# Sheet2.net
KiCad netlist of a schematic drawn in Altium Designer
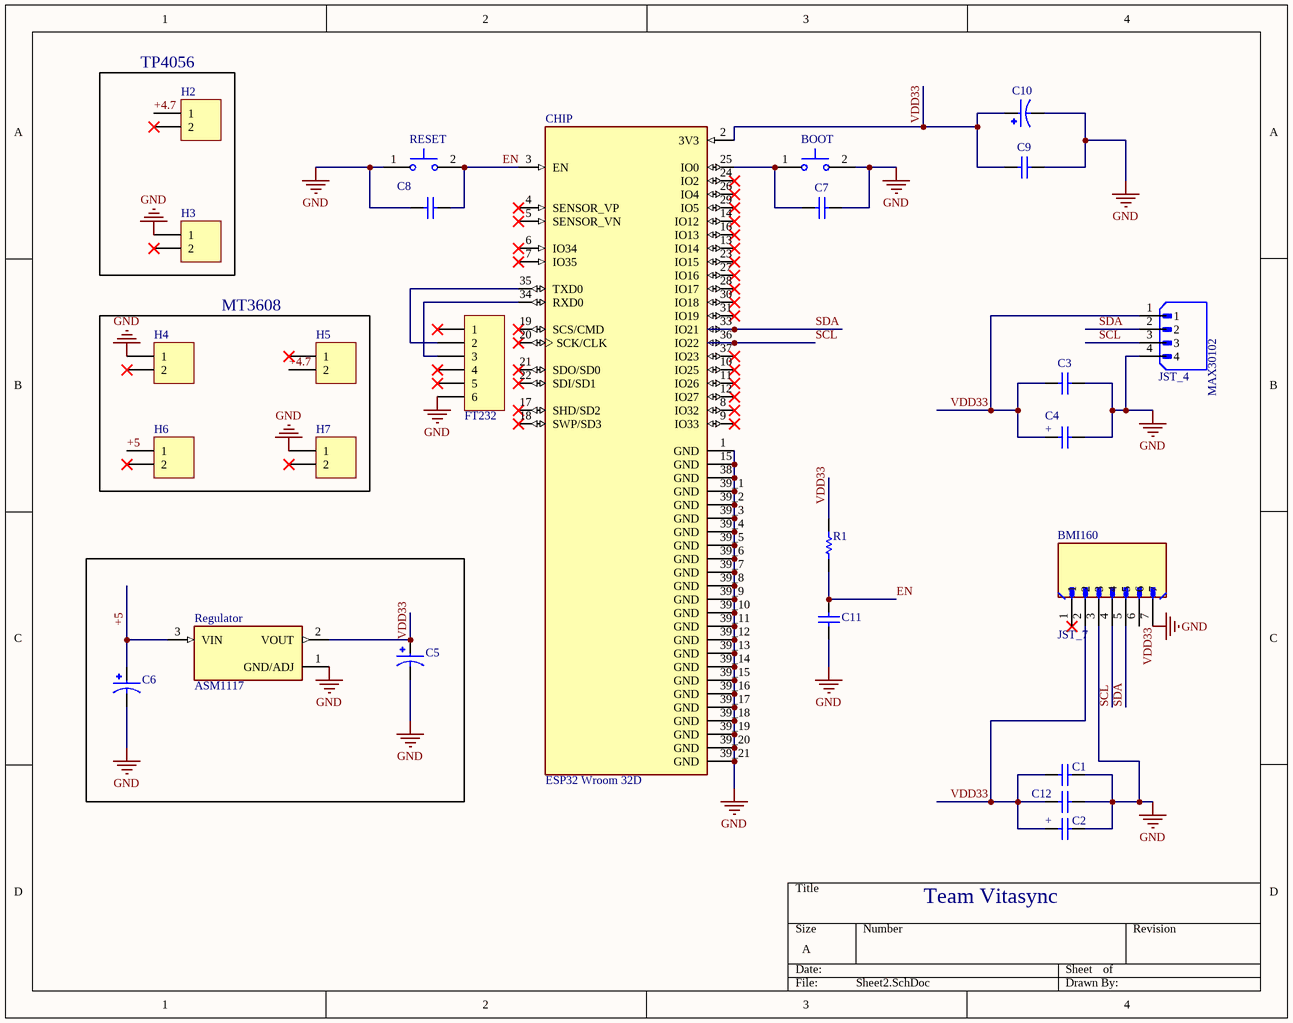
[diagram p0: Sheet2.SchDoc]

(export (version "E")
  (design (tool "Eeschema 10.0.6"))
  (components
    (comp (ref "BMI160") (value "JST_7") (footprint "JST_7") (libsource (lib "SPO2") (part "JST_7")))
    (comp (ref "BOOT")
      (value "~")
      (footprint "SW_BUTT-2")
      (description "Tactile Switches MINI PUSH BUTTON SWITCH 2-PIN QTY. 4")
      (fields (field (name "MF") "Gravitech") (field (name "MP") "BUTT-2"))
      (libsource (lib "SPO2") (part "BUTT-2"))
    )
    (comp (ref "C1")
      (value "Ceramic Capacitor")
      (footprint "Ceramic Capacitor")
      (libsource (lib "SPO2") (part "Ceramic Capacitor"))
    )
    (comp (ref "C2")
      (value "Capacitor 10uF")
      (footprint "Capacitor 10uF")
      (libsource (lib "SPO2") (part "Capacitor 10uF"))
    )
    (comp (ref "C3")
      (value "Ceramic Capacitor")
      (footprint "Ceramic Capacitor")
      (libsource (lib "SPO2") (part "Ceramic Capacitor"))
    )
    (comp (ref "C4")
      (value "Capacitor 10uF")
      (footprint "Capacitor 10uF")
      (libsource (lib "SPO2") (part "Capacitor 10uF"))
    )
    (comp (ref "C5")
      (value "EEUHD1H220")
      (footprint "CAPPRD250W50D500H1100")
      (description "Cap Aluminum Lytic 22uF 50V 20% (5 X 11mm) Radial 2.5mm 65mA 1000h 105C Bulk")
      (fields (field (name "MF") "Panasonic") (field (name "MP") "EEU-HD1H220"))
      (libsource (lib "SPO2") (part "EEUHD1H220"))
    )
    (comp (ref "C6")
      (value "EEUHD1H220")
      (footprint "CAPPRD250W50D500H1100")
      (description "Cap Aluminum Lytic 22uF 50V 20% (5 X 11mm) Radial 2.5mm 65mA 1000h 105C Bulk")
      (fields (field (name "MF") "Panasonic") (field (name "MP") "EEU-HD1H220"))
      (libsource (lib "SPO2") (part "EEUHD1H220"))
    )
    (comp (ref "C7")
      (value "Ceramic Capacitor")
      (footprint "Ceramic Capacitor")
      (libsource (lib "SPO2") (part "Ceramic Capacitor"))
    )
    (comp (ref "C8")
      (value "Ceramic Capacitor")
      (footprint "Ceramic Capacitor")
      (libsource (lib "SPO2") (part "Ceramic Capacitor"))
    )
    (comp (ref "C9")
      (value "Ceramic Capacitor")
      (footprint "Ceramic Capacitor")
      (libsource (lib "SPO2") (part "Ceramic Capacitor"))
    )
    (comp (ref "C10")
      (value "EEUHD1H220")
      (footprint "CAPPRD250W50D500H1100")
      (description "Cap Aluminum Lytic 22uF 50V 20% (5 X 11mm) Radial 2.5mm 65mA 1000h 105C Bulk")
      (fields (field (name "MF") "Panasonic") (field (name "MP") "EEU-HD1H220"))
      (libsource (lib "") (part "EEUHD1H220_1"))
    )
    (comp (ref "C11")
      (value "Ceramic Capacitor")
      (footprint "Ceramic Capacitor")
      (libsource (lib "SPO2") (part "Ceramic Capacitor"))
    )
    (comp (ref "C12")
      (value "Ceramic Capacitor")
      (footprint "Ceramic Capacitor")
      (description "10uF")
      (libsource (lib "SPO2") (part "Ceramic Capacitor"))
    )
    (comp (ref "CHIP")
      (value "ESP32 Wroom 32D")
      (footprint "ESP32 Wroom 32D")
      (libsource (lib "SPO2") (part "ESP32 Wroom 32D"))
    )
    (comp (ref "FT232")
      (value "FEMALE_HEADER_6")
      (footprint "FEMALE_HEADER_6")
      (libsource (lib "SPO2") (part "FEMALE_HEADER_6"))
    )
    (comp (ref "H2") (value "Header_2") (footprint "HEADER_2") (libsource (lib "SPO2") (part "Header_2")))
    (comp (ref "H3") (value "Header_2") (footprint "HEADER_2") (libsource (lib "SPO2") (part "Header_2")))
    (comp (ref "H4") (value "Header_2") (footprint "HEADER_2") (libsource (lib "SPO2") (part "Header_2")))
    (comp (ref "H5") (value "Header_2") (footprint "HEADER_2") (libsource (lib "SPO2") (part "Header_2")))
    (comp (ref "H6") (value "Header_2") (footprint "HEADER_2") (libsource (lib "SPO2") (part "Header_2")))
    (comp (ref "H7") (value "Header_2") (footprint "HEADER_2") (libsource (lib "SPO2") (part "Header_2")))
    (comp (ref "MAX30102") (value "JST_4") (footprint "JST_4") (libsource (lib "SPO2") (part "JST_4")))
    (comp (ref "R1")
      (value "resistor")
      (footprint "Resistor")
      (description "10k,0.25W")
      (libsource (lib "SPO2") (part "resistor"))
    )
    (comp (ref "Regulator") (value "ASM1117") (footprint "ASM1117") (libsource (lib "SPO2") (part "ASM1117")))
    (comp (ref "RESET")
      (value "BUTT-2")
      (footprint "SW_BUTT-2")
      (description "Tactile Switches MINI PUSH BUTTON SWITCH 2-PIN QTY. 4")
      (fields (field (name "MF") "Gravitech"))
      (libsource (lib "SPO2") (part "BUTT-2"))
    )
  )
  (nets
    (net (code "1") (name "/+4.7") (class "Default")
      (node (ref "H2") (pin "1") (pinfunction "1_1") (pintype "passive"))
      (node (ref "H5") (pin "2") (pinfunction "2_2") (pintype "passive"))
    )
    (net (code "2") (name "/+5") (class "Default")
      (node (ref "C6") (pin "P") (pinfunction "P_P") (pintype "passive"))
      (node (ref "H6") (pin "1") (pinfunction "1_1") (pintype "passive"))
      (node (ref "Regulator") (pin "3") (pinfunction "VIN_3") (pintype "input"))
    )
    (net (code "3") (name "/EN") (class "Default")
      (node (ref "C11") (pin "2") (pinfunction "2_2") (pintype "passive"))
      (node (ref "C8") (pin "2") (pinfunction "2_2") (pintype "passive"))
      (node (ref "CHIP") (pin "3") (pinfunction "EN_3") (pintype "input"))
      (node (ref "R1") (pin "1") (pinfunction "1_1") (pintype "passive"))
      (node (ref "RESET") (pin "2") (pinfunction "2_2") (pintype "passive"))
    )
    (net (code "4") (name "/SCL") (class "Default")
      (node (ref "BMI160") (pin "4") (pinfunction "4_4") (pintype "passive"))
      (node (ref "CHIP") (pin "36") (pinfunction "IO22_36") (pintype "bidirectional"))
      (node (ref "MAX30102") (pin "3") (pinfunction "3_3") (pintype "passive"))
    )
    (net (code "5") (name "/SDA") (class "Default")
      (node (ref "BMI160") (pin "5") (pinfunction "5_5") (pintype "passive"))
      (node (ref "CHIP") (pin "33") (pinfunction "IO21_33") (pintype "bidirectional"))
      (node (ref "MAX30102") (pin "2") (pinfunction "2_2") (pintype "passive"))
    )
    (net (code "6") (name "/VDD33") (class "Default")
      (node (ref "BMI160") (pin "2") (pinfunction "2_2") (pintype "passive"))
      (node (ref "BMI160") (pin "6") (pinfunction "6_6") (pintype "passive"))
      (node (ref "C1") (pin "1") (pinfunction "1_1") (pintype "passive"))
      (node (ref "C10") (pin "P") (pinfunction "P_P") (pintype "passive"))
      (node (ref "C12") (pin "1") (pinfunction "1_1") (pintype "passive"))
      (node (ref "C2") (pin "+") (pinfunction "+_+") (pintype "passive"))
      (node (ref "C3") (pin "1") (pinfunction "1_1") (pintype "passive"))
      (node (ref "C4") (pin "+") (pinfunction "+_+") (pintype "passive"))
      (node (ref "C5") (pin "P") (pinfunction "P_P") (pintype "passive"))
      (node (ref "C9") (pin "1") (pinfunction "1_1") (pintype "passive"))
      (node (ref "CHIP") (pin "2") (pinfunction "3V3_2") (pintype "input"))
      (node (ref "MAX30102") (pin "1") (pinfunction "1_1") (pintype "passive"))
      (node (ref "R1") (pin "2") (pinfunction "2_2") (pintype "passive"))
      (node (ref "Regulator") (pin "2") (pinfunction "VOUT_2") (pintype "output"))
    )
    (net (code "7") (name "GND") (class "Default")
      (node (ref "BMI160") (pin "3") (pinfunction "3_3") (pintype "passive"))
      (node (ref "BMI160") (pin "7") (pinfunction "7_7") (pintype "passive"))
      (node (ref "BOOT") (pin "2") (pinfunction "2_2") (pintype "passive"))
      (node (ref "C1") (pin "2") (pinfunction "2_2") (pintype "passive"))
      (node (ref "C10") (pin "N") (pinfunction "N_N") (pintype "passive"))
      (node (ref "C11") (pin "1") (pinfunction "1_1") (pintype "passive"))
      (node (ref "C12") (pin "2") (pinfunction "2_2") (pintype "passive"))
      (node (ref "C2") (pin "-") (pinfunction "-_-") (pintype "passive"))
      (node (ref "C3") (pin "2") (pinfunction "2_2") (pintype "passive"))
      (node (ref "C4") (pin "-") (pinfunction "-_-") (pintype "passive"))
      (node (ref "C5") (pin "N") (pinfunction "N_N") (pintype "passive"))
      (node (ref "C6") (pin "N") (pinfunction "N_N") (pintype "passive"))
      (node (ref "C7") (pin "2") (pinfunction "2_2") (pintype "passive"))
      (node (ref "C8") (pin "1") (pinfunction "1_1") (pintype "passive"))
      (node (ref "C9") (pin "2") (pinfunction "2_2") (pintype "passive"))
      (node (ref "CHIP") (pin "1") (pinfunction "GND_1") (pintype "power_in"))
      (node (ref "CHIP") (pin "15") (pinfunction "GND_15") (pintype "power_in"))
      (node (ref "CHIP") (pin "38") (pinfunction "GND_38") (pintype "power_in"))
      (node (ref "CHIP") (pin "39_1") (pinfunction "GND_39_1") (pintype "power_in"))
      (node (ref "CHIP") (pin "39_10") (pinfunction "GND_39_10") (pintype "power_in"))
      (node (ref "CHIP") (pin "39_11") (pinfunction "GND_39_11") (pintype "power_in"))
      (node (ref "CHIP") (pin "39_12") (pinfunction "GND_39_12") (pintype "power_in"))
      (node (ref "CHIP") (pin "39_13") (pinfunction "GND_39_13") (pintype "power_in"))
      (node (ref "CHIP") (pin "39_14") (pinfunction "GND_39_14") (pintype "power_in"))
      (node (ref "CHIP") (pin "39_15") (pinfunction "GND_39_15") (pintype "power_in"))
      (node (ref "CHIP") (pin "39_16") (pinfunction "GND_39_16") (pintype "power_in"))
      (node (ref "CHIP") (pin "39_17") (pinfunction "GND_39_17") (pintype "power_in"))
      (node (ref "CHIP") (pin "39_18") (pinfunction "GND_39_18") (pintype "power_in"))
      (node (ref "CHIP") (pin "39_19") (pinfunction "GND_39_19") (pintype "power_in"))
      (node (ref "CHIP") (pin "39_2") (pinfunction "GND_39_2") (pintype "power_in"))
      (node (ref "CHIP") (pin "39_20") (pinfunction "GND_39_20") (pintype "power_in"))
      (node (ref "CHIP") (pin "39_21") (pinfunction "GND_39_21") (pintype "power_in"))
      (node (ref "CHIP") (pin "39_3") (pinfunction "GND_39_3") (pintype "power_in"))
      (node (ref "CHIP") (pin "39_4") (pinfunction "GND_39_4") (pintype "power_in"))
      (node (ref "CHIP") (pin "39_5") (pinfunction "GND_39_5") (pintype "power_in"))
      (node (ref "CHIP") (pin "39_6") (pinfunction "GND_39_6") (pintype "power_in"))
      (node (ref "CHIP") (pin "39_7") (pinfunction "GND_39_7") (pintype "power_in"))
      (node (ref "CHIP") (pin "39_8") (pinfunction "GND_39_8") (pintype "power_in"))
      (node (ref "CHIP") (pin "39_9") (pinfunction "GND_39_9") (pintype "power_in"))
      (node (ref "FT232") (pin "6") (pinfunction "6_6") (pintype "passive"))
      (node (ref "H3") (pin "1") (pinfunction "1_1") (pintype "passive"))
      (node (ref "H4") (pin "1") (pinfunction "1_1") (pintype "passive"))
      (node (ref "H7") (pin "1") (pinfunction "1_1") (pintype "passive"))
      (node (ref "MAX30102") (pin "4") (pinfunction "4_4") (pintype "passive"))
      (node (ref "RESET") (pin "1") (pinfunction "1_1") (pintype "passive"))
      (node (ref "Regulator") (pin "1") (pinfunction "GND/ADJ_1") (pintype "power_in"))
    )
    (net (code "8") (name "Net-(CHIP-IO0)") (class "Default")
      (node (ref "BOOT") (pin "1") (pinfunction "1_1") (pintype "passive"))
      (node (ref "C7") (pin "1") (pinfunction "1_1") (pintype "passive"))
      (node (ref "CHIP") (pin "25") (pinfunction "IO0_25") (pintype "bidirectional"))
    )
    (net (code "9") (name "Net-(CHIP-RXD0)") (class "Default")
      (node (ref "CHIP") (pin "34") (pinfunction "RXD0_34") (pintype "bidirectional"))
      (node (ref "FT232") (pin "3") (pinfunction "3_3") (pintype "passive"))
    )
    (net (code "10") (name "Net-(CHIP-TXD0)") (class "Default")
      (node (ref "CHIP") (pin "35") (pinfunction "TXD0_35") (pintype "bidirectional"))
      (node (ref "FT232") (pin "2") (pinfunction "2_2") (pintype "passive"))
    )
    (net (code "11") (name "unconnected-(BMI160-Pad1)") (class "Default")
      (node (ref "BMI160") (pin "1") (pinfunction "1_1") (pintype "passive+no_connect"))
    )
    (net (code "12") (name "unconnected-(CHIP-IO2-Pad24)") (class "Default")
      (node (ref "CHIP") (pin "24") (pinfunction "IO2_24") (pintype "bidirectional+no_connect"))
    )
    (net (code "13") (name "unconnected-(CHIP-IO4-Pad26)") (class "Default")
      (node (ref "CHIP") (pin "26") (pinfunction "IO4_26") (pintype "bidirectional+no_connect"))
    )
    (net (code "14") (name "unconnected-(CHIP-IO5-Pad29)") (class "Default")
      (node (ref "CHIP") (pin "29") (pinfunction "IO5_29") (pintype "bidirectional+no_connect"))
    )
    (net (code "15") (name "unconnected-(CHIP-IO12-Pad14)") (class "Default")
      (node (ref "CHIP") (pin "14") (pinfunction "IO12_14") (pintype "bidirectional+no_connect"))
    )
    (net (code "16") (name "unconnected-(CHIP-IO13-Pad16)") (class "Default")
      (node (ref "CHIP") (pin "16") (pinfunction "IO13_16") (pintype "bidirectional+no_connect"))
    )
    (net (code "17") (name "unconnected-(CHIP-IO14-Pad13)") (class "Default")
      (node (ref "CHIP") (pin "13") (pinfunction "IO14_13") (pintype "bidirectional+no_connect"))
    )
    (net (code "18") (name "unconnected-(CHIP-IO15-Pad23)") (class "Default")
      (node (ref "CHIP") (pin "23") (pinfunction "IO15_23") (pintype "bidirectional+no_connect"))
    )
    (net (code "19") (name "unconnected-(CHIP-IO16-Pad27)") (class "Default")
      (node (ref "CHIP") (pin "27") (pinfunction "IO16_27") (pintype "bidirectional+no_connect"))
    )
    (net (code "20") (name "unconnected-(CHIP-IO17-Pad28)") (class "Default")
      (node (ref "CHIP") (pin "28") (pinfunction "IO17_28") (pintype "bidirectional+no_connect"))
    )
    (net (code "21") (name "unconnected-(CHIP-IO18-Pad30)") (class "Default")
      (node (ref "CHIP") (pin "30") (pinfunction "IO18_30") (pintype "bidirectional+no_connect"))
    )
    (net (code "22") (name "unconnected-(CHIP-IO19-Pad31)") (class "Default")
      (node (ref "CHIP") (pin "31") (pinfunction "IO19_31") (pintype "bidirectional+no_connect"))
    )
    (net (code "23") (name "unconnected-(CHIP-IO23-Pad37)") (class "Default")
      (node (ref "CHIP") (pin "37") (pinfunction "IO23_37") (pintype "bidirectional+no_connect"))
    )
    (net (code "24") (name "unconnected-(CHIP-IO25-Pad10)") (class "Default")
      (node (ref "CHIP") (pin "10") (pinfunction "IO25_10") (pintype "bidirectional+no_connect"))
    )
    (net (code "25") (name "unconnected-(CHIP-IO26-Pad11)") (class "Default")
      (node (ref "CHIP") (pin "11") (pinfunction "IO26_11") (pintype "bidirectional+no_connect"))
    )
    (net (code "26") (name "unconnected-(CHIP-IO27-Pad12)") (class "Default")
      (node (ref "CHIP") (pin "12") (pinfunction "IO27_12") (pintype "bidirectional+no_connect"))
    )
    (net (code "27") (name "unconnected-(CHIP-IO32-Pad8)") (class "Default")
      (node (ref "CHIP") (pin "8") (pinfunction "IO32_8") (pintype "bidirectional+no_connect"))
    )
    (net (code "28") (name "unconnected-(CHIP-IO33-Pad9)") (class "Default")
      (node (ref "CHIP") (pin "9") (pinfunction "IO33_9") (pintype "bidirectional+no_connect"))
    )
    (net (code "29") (name "unconnected-(CHIP-IO34-Pad6)") (class "Default")
      (node (ref "CHIP") (pin "6") (pinfunction "IO34_6") (pintype "input+no_connect"))
    )
    (net (code "30") (name "unconnected-(CHIP-IO35-Pad7)") (class "Default")
      (node (ref "CHIP") (pin "7") (pinfunction "IO35_7") (pintype "input+no_connect"))
    )
    (net (code "31") (name "unconnected-(CHIP-SCK{slash}CLK-Pad20)") (class "Default")
      (node (ref "CHIP") (pin "20") (pinfunction "SCK/CLK_20") (pintype "bidirectional+no_connect"))
    )
    (net (code "32") (name "unconnected-(CHIP-SCS{slash}CMD-Pad19)") (class "Default")
      (node (ref "CHIP") (pin "19") (pinfunction "SCS/CMD_19") (pintype "bidirectional+no_connect"))
    )
    (net (code "33") (name "unconnected-(CHIP-SDI{slash}SD1-Pad22)") (class "Default")
      (node (ref "CHIP") (pin "22") (pinfunction "SDI/SD1_22") (pintype "bidirectional+no_connect"))
    )
    (net (code "34") (name "unconnected-(CHIP-SDO{slash}SD0-Pad21)") (class "Default")
      (node (ref "CHIP") (pin "21") (pinfunction "SDO/SD0_21") (pintype "bidirectional+no_connect"))
    )
    (net (code "35") (name "unconnected-(CHIP-SENSOR_VN-Pad5)") (class "Default")
      (node (ref "CHIP") (pin "5") (pinfunction "SENSOR_VN_5") (pintype "input+no_connect"))
    )
    (net (code "36") (name "unconnected-(CHIP-SENSOR_VP-Pad4)") (class "Default")
      (node (ref "CHIP") (pin "4") (pinfunction "SENSOR_VP_4") (pintype "input+no_connect"))
    )
    (net (code "37") (name "unconnected-(CHIP-SHD{slash}SD2-Pad17)") (class "Default")
      (node (ref "CHIP") (pin "17") (pinfunction "SHD/SD2_17") (pintype "bidirectional+no_connect"))
    )
    (net (code "38") (name "unconnected-(CHIP-SWP{slash}SD3-Pad18)") (class "Default")
      (node (ref "CHIP") (pin "18") (pinfunction "SWP/SD3_18") (pintype "bidirectional+no_connect"))
    )
    (net (code "39") (name "unconnected-(FT232-Pad1)") (class "Default")
      (node (ref "FT232") (pin "1") (pinfunction "1_1") (pintype "passive+no_connect"))
    )
    (net (code "40") (name "unconnected-(FT232-Pad4)") (class "Default")
      (node (ref "FT232") (pin "4") (pinfunction "4_4") (pintype "passive+no_connect"))
    )
    (net (code "41") (name "unconnected-(FT232-Pad5)") (class "Default")
      (node (ref "FT232") (pin "5") (pinfunction "5_5") (pintype "passive+no_connect"))
    )
    (net (code "42") (name "unconnected-(H2-Pad2)") (class "Default")
      (node (ref "H2") (pin "2") (pinfunction "2_2") (pintype "passive+no_connect"))
    )
    (net (code "43") (name "unconnected-(H3-Pad2)") (class "Default")
      (node (ref "H3") (pin "2") (pinfunction "2_2") (pintype "passive+no_connect"))
    )
    (net (code "44") (name "unconnected-(H4-Pad2)") (class "Default")
      (node (ref "H4") (pin "2") (pinfunction "2_2") (pintype "passive+no_connect"))
    )
    (net (code "45") (name "unconnected-(H5-Pad1)") (class "Default")
      (node (ref "H5") (pin "1") (pinfunction "1_1") (pintype "passive+no_connect"))
    )
    (net (code "46") (name "unconnected-(H6-Pad2)") (class "Default")
      (node (ref "H6") (pin "2") (pinfunction "2_2") (pintype "passive+no_connect"))
    )
    (net (code "47") (name "unconnected-(H7-Pad2)") (class "Default")
      (node (ref "H7") (pin "2") (pinfunction "2_2") (pintype "passive+no_connect"))
    )
  )
)
